# Power_Supply.net
KiCad netlist of a schematic drawn in Altium Designer
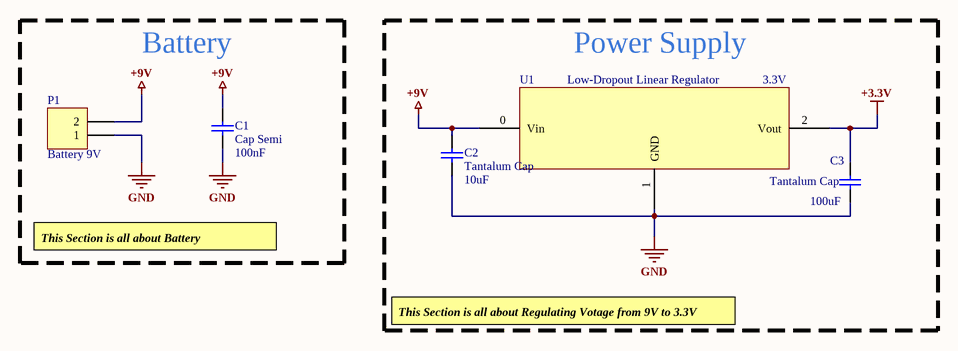
[diagram p0: Power_Supply.SchDoc]

(export (version "E")
  (design (tool "Eeschema 10.0.6"))
  (components
    (comp (ref "C1")
      (value "Cap Semi")
      (footprint "C1206")
      (description "Capacitor (Semiconductor SIM Model)")
      (fields (field (name "ALTIUM_VALUE") "100nF") (field (name "PUBLISHER") "Altium Limited"))
      (libsource (lib "Miscellaneous Devices") (part "Cap Semi"))
    )
    (comp (ref "C2")
      (value "Tantalum Cap")
      (footprint "C1206")
      (description "Capacitor (Semiconductor SIM Model)")
      (fields (field (name "ALTIUM_VALUE") "10uF") (field (name "PUBLISHER") "Altium Limited"))
      (libsource (lib "Miscellaneous Devices") (part "Cap Semi"))
    )
    (comp (ref "C3")
      (value "Tantalum Cap")
      (footprint "C1206")
      (description "Capacitor (Semiconductor SIM Model)")
      (fields (field (name "ALTIUM_VALUE") "100uF") (field (name "PUBLISHER") "Altium Limited"))
      (libsource (lib "Miscellaneous Devices") (part "Cap Semi"))
    )
    (comp (ref "P1")
      (value "Battery 9V")
      (footprint "HDR1X2H")
      (description "Header, 2-Pin, Right Angle")
      (fields (field (name "VOLTAGE") "9V") (field (name "PUBLISHER") "Altium Limited"))
      (libsource (lib "Miscellaneous Connectors") (part "Header 2H"))
    )
    (comp (ref "U1")
      (value "Low-Dropout Linear Regulator")
      (footprint "4-Pin SOT")
      (fields (field (name "OUTPUT VOLTAGE") "3.3V"))
      (libsource (lib "LM1117_Voltage_Regulator") (part "LM1117"))
    )
  )
  (nets
    (net (code "1") (name "+3.3V") (class "Default")
      (node (ref "C3") (pin "2") (pinfunction "2_2") (pintype "passive"))
      (node (ref "U1") (pin "2") (pinfunction "Vout_2") (pintype "passive"))
    )
    (net (code "2") (name "+9V") (class "Default")
      (node (ref "C1") (pin "2") (pinfunction "2_2") (pintype "passive"))
      (node (ref "C2") (pin "2") (pinfunction "2_2") (pintype "passive"))
      (node (ref "P1") (pin "2") (pinfunction "2_2") (pintype "passive"))
      (node (ref "U1") (pin "0") (pinfunction "Vin_0") (pintype "passive"))
    )
    (net (code "3") (name "GND") (class "Default")
      (node (ref "C1") (pin "1") (pinfunction "1_1") (pintype "passive"))
      (node (ref "C2") (pin "1") (pinfunction "1_1") (pintype "passive"))
      (node (ref "C3") (pin "1") (pinfunction "1_1") (pintype "passive"))
      (node (ref "P1") (pin "1") (pinfunction "1_1") (pintype "passive"))
      (node (ref "U1") (pin "1") (pinfunction "GND_1") (pintype "passive"))
    )
  )
)
